# iot-tracker-A.net
KiCad netlist of a schematic drawn in EAGLE
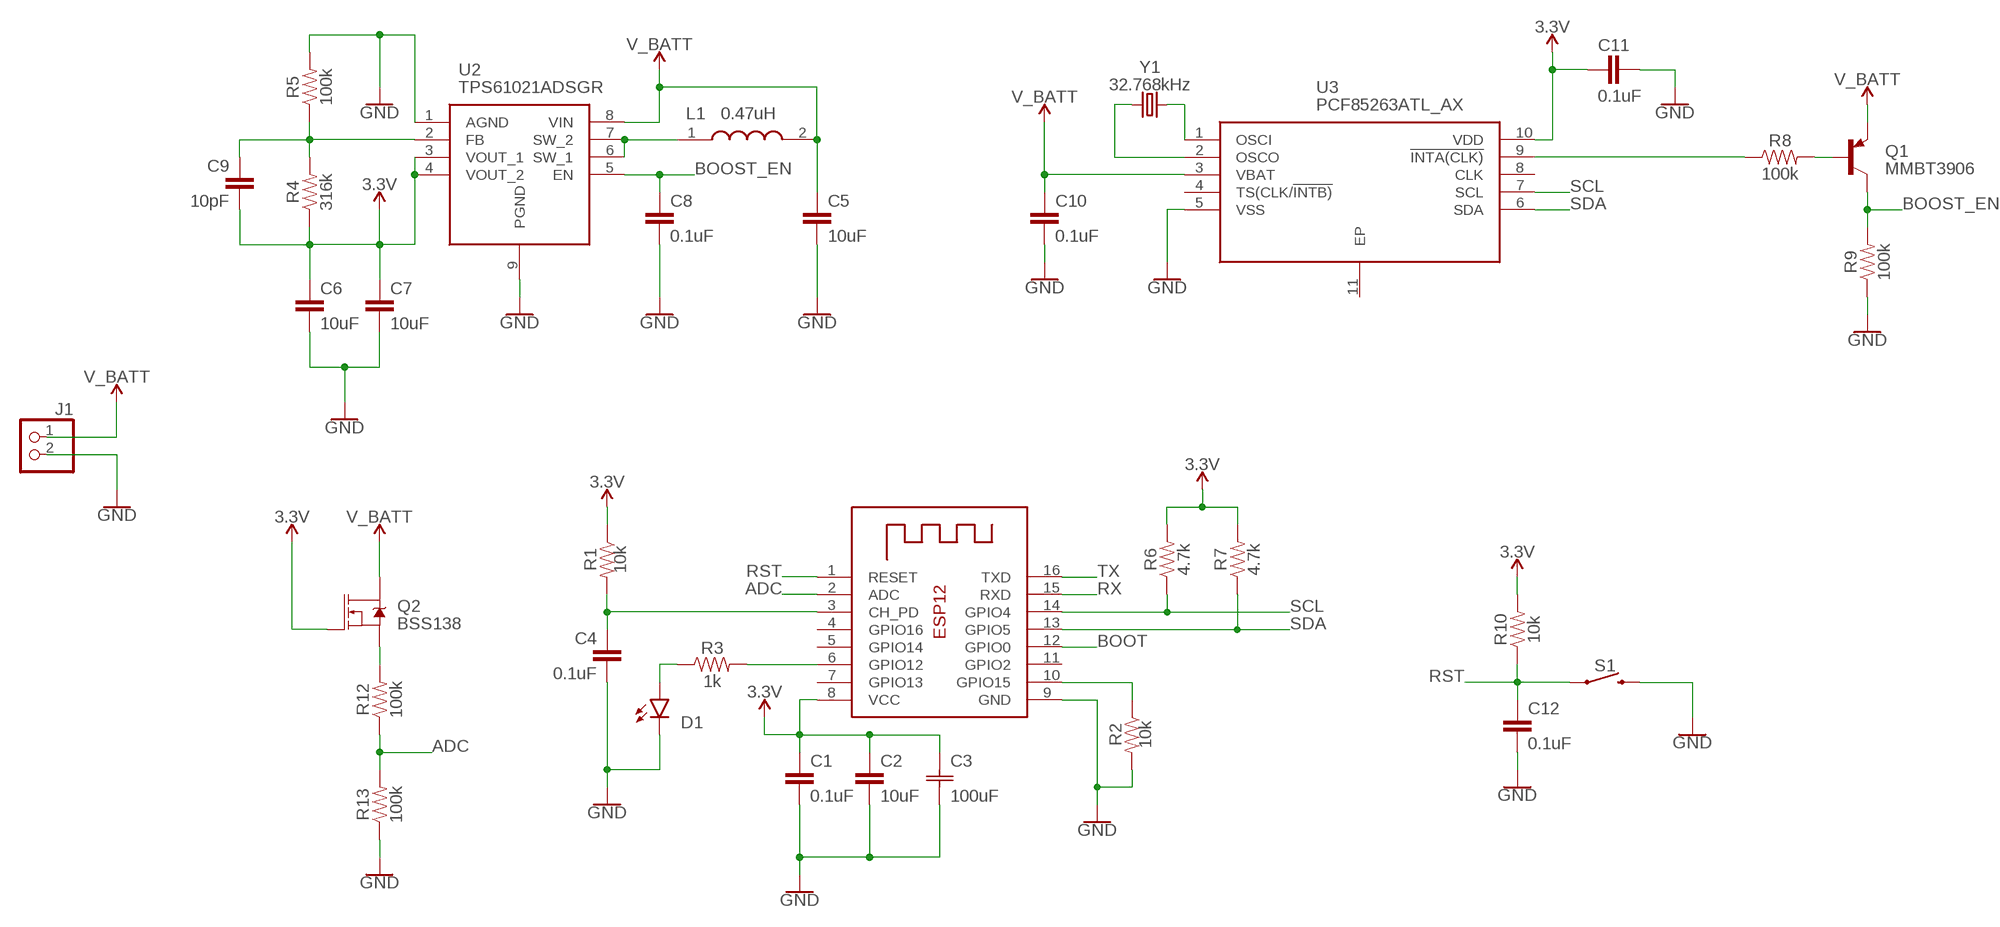
[diagram p0: schematic, sheet 1]

(export (version "E")
  (design (tool "Eeschema 10.0.6"))
  (components
    (comp (ref "C1")
      (value "0.1uF")
      (footprint "eagle-import:0603")
      (libsource (lib "eagle-import") (part "0.1UF-0603-25V-(+80/-20%)"))
    )
    (comp (ref "C2")
      (value "10uF")
      (footprint "eagle-import:0603")
      (libsource (lib "eagle-import") (part "10UF-0603-6.3V-20%"))
    )
    (comp (ref "C3")
      (value "100uF")
      (footprint "eagle-import:F93-C")
      (fields (field (name "MANUFACTURER_PART_NUMBER") "F930J107MBA"))
      (libsource (lib "eagle-import") (part "F930J107MBA"))
    )
    (comp (ref "C4")
      (value "0.1uF")
      (footprint "eagle-import:0603")
      (libsource (lib "eagle-import") (part "0.1UF-0603-25V-(+80/-20%)"))
    )
    (comp (ref "C5")
      (value "10uF")
      (footprint "eagle-import:0603")
      (libsource (lib "eagle-import") (part "10UF-0603-6.3V-20%"))
    )
    (comp (ref "C6")
      (value "10uF")
      (footprint "eagle-import:0603")
      (libsource (lib "eagle-import") (part "10UF-0603-6.3V-20%"))
    )
    (comp (ref "C7")
      (value "10uF")
      (footprint "eagle-import:0603")
      (libsource (lib "eagle-import") (part "10UF-0603-6.3V-20%"))
    )
    (comp (ref "C8")
      (value "0.1uF")
      (footprint "eagle-import:0603")
      (libsource (lib "eagle-import") (part "0.1UF-0603-25V-(+80/-20%)"))
    )
    (comp (ref "C9")
      (value "10pF")
      (footprint "eagle-import:0603")
      (libsource (lib "eagle-import") (part "10PF-0603-50V-5%"))
    )
    (comp (ref "C10")
      (value "0.1uF")
      (footprint "eagle-import:0603")
      (libsource (lib "eagle-import") (part "0.1UF-0603-25V-(+80/-20%)"))
    )
    (comp (ref "C11")
      (value "0.1uF")
      (footprint "eagle-import:0603")
      (libsource (lib "eagle-import") (part "0.1UF-0603-25V-(+80/-20%)"))
    )
    (comp (ref "C12")
      (value "0.1uF")
      (footprint "eagle-import:0603")
      (libsource (lib "eagle-import") (part "0.1UF-0603-25V-(+80/-20%)"))
    )
    (comp (ref "D1")
      (value "LED0603")
      (footprint "eagle-import:LED-0603")
      (libsource (lib "eagle-import") (part "LED0603"))
    )
    (comp (ref "J1")
      (value "PINHD-1X2")
      (footprint "eagle-import:1X02")
      (libsource (lib "eagle-import") (part "PINHD-1X2"))
    )
    (comp (ref "L1")
      (value "0.47uH")
      (footprint "eagle-import:INDC2520X120N")
      (fields
        (field (name "MANUFACTURER_PART_NUMBER") "DFE252012P-R47M=P2")
        (field (name "MOUSER_PART_NUMBER") "81-DFE252012P-R47MP2")
      )
      (libsource (lib "eagle-import") (part "DFE252012P-R47M=P2"))
    )
    (comp (ref "Q1")
      (value "MMBT3906")
      (footprint "eagle-import:SOT23-BEC")
      (libsource (lib "eagle-import") (part "MMBT3906SMDLT1"))
    )
    (comp (ref "Q2")
      (value "BSS138")
      (footprint "eagle-import:SOT23-3")
      (libsource (lib "eagle-import") (part "MOSFET-NCH-BSS138"))
    )
    (comp (ref "R1")
      (value "10k")
      (footprint "eagle-import:0603")
      (libsource (lib "eagle-import") (part "10KOHM-0603-1/10W-1%"))
    )
    (comp (ref "R2")
      (value "10k")
      (footprint "eagle-import:0603")
      (libsource (lib "eagle-import") (part "10KOHM-0603-1/10W-1%"))
    )
    (comp (ref "R3")
      (value "1k")
      (footprint "eagle-import:0603")
      (libsource (lib "eagle-import") (part "1KOHM-0603-1/10W-1%"))
    )
    (comp (ref "R4")
      (value "316k")
      (footprint "eagle-import:0603")
      (libsource (lib "eagle-import") (part "300KOHM-0603-1/10W-1%"))
    )
    (comp (ref "R5")
      (value "100k")
      (footprint "eagle-import:0603")
      (libsource (lib "eagle-import") (part "100KOHM-0603-1/10W-1%"))
    )
    (comp (ref "R6")
      (value "4.7k")
      (footprint "eagle-import:0603")
      (libsource (lib "eagle-import") (part "4.7KOHM-0603-1/10W-1%"))
    )
    (comp (ref "R7")
      (value "4.7k")
      (footprint "eagle-import:0603")
      (libsource (lib "eagle-import") (part "4.7KOHM-0603-1/10W-1%"))
    )
    (comp (ref "R8")
      (value "100k")
      (footprint "eagle-import:0603")
      (libsource (lib "eagle-import") (part "100KOHM-0603-1/10W-1%"))
    )
    (comp (ref "R9")
      (value "100k")
      (footprint "eagle-import:0603")
      (libsource (lib "eagle-import") (part "100KOHM-0603-1/10W-1%"))
    )
    (comp (ref "R10")
      (value "10k")
      (footprint "eagle-import:0603")
      (libsource (lib "eagle-import") (part "10KOHM-0603-1/10W-1%"))
    )
    (comp (ref "R12")
      (value "100k")
      (footprint "eagle-import:0603")
      (libsource (lib "eagle-import") (part "100KOHM-0603-1/10W-1%"))
    )
    (comp (ref "R13")
      (value "100k")
      (footprint "eagle-import:0603")
      (libsource (lib "eagle-import") (part "100KOHM-0603-1/10W-1%"))
    )
    (comp (ref "S1")
      (value "MOMENTARY-SWITCH-SPST-SMD-4.6X2.8MM")
      (footprint "eagle-import:TACTILE_SWITCH_SMD_4.6X2.8MM")
      (libsource (lib "eagle-import") (part "MOMENTARY-SWITCH-SPST-SMD-4.6X2.8MM"))
    )
    (comp (ref "U1")
      (value "ESP-12")
      (footprint "eagle-import:ESP-12")
      (libsource (lib "eagle-import") (part "ESP-12"))
    )
    (comp (ref "U2")
      (value "TPS61021ADSGR")
      (footprint "eagle-import:SON50P200X200X80-9N")
      (fields (field (name "MOUSER_PART_NUMBER") "595-TPS61021ADSGR"))
      (libsource (lib "eagle-import") (part "TPS61021ADSGR"))
    )
    (comp (ref "U3")
      (value "PCF85263ATL_AX")
      (footprint "eagle-import:SON50P260X260X50-11N")
      (fields
        (field (name "MANUFACTURER_PART_NUMBER") "PCF85263ATL/AX")
        (field (name "MOUSER_PART_NUMBER") "771-PCF85263ATL/AX")
      )
      (libsource (lib "eagle-import") (part "PCF85263ATL_AX"))
    )
    (comp (ref "Y1")
      (value "32.768kHz")
      (footprint "eagle-import:CRYSTAL-SMD-3.2X1.5MM")
      (libsource (lib "eagle-import") (part "CRYSTAL-32.768KHZSMD-3.2X1.5"))
    )
  )
  (nets
    (net (code "1") (name "/ADC") (class "Default")
      (node (ref "R12") (pin "1") (pinfunction "1_1") (pintype "passive"))
      (node (ref "R13") (pin "2") (pinfunction "2_2") (pintype "passive"))
      (node (ref "U1") (pin "2") (pinfunction "ADC_2") (pintype "passive"))
    )
    (net (code "2") (name "/BOOST_EN") (class "Default")
      (node (ref "C8") (pin "1") (pinfunction "1_1") (pintype "passive"))
      (node (ref "Q1") (pin "C") (pinfunction "C_C") (pintype "passive"))
      (node (ref "R9") (pin "2") (pinfunction "2_2") (pintype "passive"))
      (node (ref "U2") (pin "5") (pinfunction "EN_5") (pintype "input"))
    )
    (net (code "3") (name "/BOOT") (class "Default")
      (node (ref "U1") (pin "12") (pinfunction "GPIO0_12") (pintype "bidirectional"))
    )
    (net (code "4") (name "/RST") (class "Default")
      (node (ref "C12") (pin "1") (pinfunction "1_1") (pintype "passive"))
      (node (ref "R10") (pin "1") (pinfunction "1_1") (pintype "passive"))
      (node (ref "S1") (pin "1") (pinfunction "1_1") (pintype "passive"))
      (node (ref "S1") (pin "2") (pinfunction "1_2") (pintype "passive"))
      (node (ref "U1") (pin "1") (pinfunction "RESET_1") (pintype "input"))
    )
    (net (code "5") (name "/RX") (class "Default")
      (node (ref "U1") (pin "15") (pinfunction "RXD_15") (pintype "input"))
    )
    (net (code "6") (name "/SCL") (class "Default")
      (node (ref "R6") (pin "1") (pinfunction "1_1") (pintype "passive"))
      (node (ref "U1") (pin "14") (pinfunction "GPIO4_14") (pintype "bidirectional"))
      (node (ref "U3") (pin "7") (pinfunction "SCL_7") (pintype "bidirectional"))
    )
    (net (code "7") (name "/SDA") (class "Default")
      (node (ref "R7") (pin "1") (pinfunction "1_1") (pintype "passive"))
      (node (ref "U1") (pin "13") (pinfunction "GPIO5_13") (pintype "bidirectional"))
      (node (ref "U3") (pin "6") (pinfunction "SDA_6") (pintype "bidirectional"))
    )
    (net (code "8") (name "/TX") (class "Default")
      (node (ref "U1") (pin "16") (pinfunction "TXD_16") (pintype "output"))
    )
    (net (code "9") (name "3.3V") (class "Default")
      (node (ref "C1") (pin "1") (pinfunction "1_1") (pintype "passive"))
      (node (ref "C11") (pin "2") (pinfunction "2_2") (pintype "passive"))
      (node (ref "C2") (pin "1") (pinfunction "1_1") (pintype "passive"))
      (node (ref "C3") (pin "1") (pinfunction "1_1") (pintype "passive"))
      (node (ref "C6") (pin "1") (pinfunction "1_1") (pintype "passive"))
      (node (ref "C7") (pin "1") (pinfunction "1_1") (pintype "passive"))
      (node (ref "C9") (pin "2") (pinfunction "2_2") (pintype "passive"))
      (node (ref "Q2") (pin "1") (pinfunction "G_1") (pintype "bidirectional"))
      (node (ref "R1") (pin "1") (pinfunction "1_1") (pintype "passive"))
      (node (ref "R10") (pin "2") (pinfunction "2_2") (pintype "passive"))
      (node (ref "R4") (pin "1") (pinfunction "1_1") (pintype "passive"))
      (node (ref "R6") (pin "2") (pinfunction "2_2") (pintype "passive"))
      (node (ref "R7") (pin "2") (pinfunction "2_2") (pintype "passive"))
      (node (ref "U1") (pin "8") (pinfunction "VCC_8") (pintype "power_in"))
      (node (ref "U2") (pin "3") (pinfunction "VOUT_1_3") (pintype "power_in"))
      (node (ref "U2") (pin "4") (pinfunction "VOUT_2_4") (pintype "power_in"))
      (node (ref "U3") (pin "10") (pinfunction "VDD_10") (pintype "power_in"))
    )
    (net (code "10") (name "GND") (class "Default")
      (node (ref "C1") (pin "2") (pinfunction "2_2") (pintype "passive"))
      (node (ref "C10") (pin "2") (pinfunction "2_2") (pintype "passive"))
      (node (ref "C11") (pin "1") (pinfunction "1_1") (pintype "passive"))
      (node (ref "C12") (pin "2") (pinfunction "2_2") (pintype "passive"))
      (node (ref "C2") (pin "2") (pinfunction "2_2") (pintype "passive"))
      (node (ref "C3") (pin "2") (pinfunction "2_2") (pintype "passive"))
      (node (ref "C4") (pin "2") (pinfunction "2_2") (pintype "passive"))
      (node (ref "C5") (pin "2") (pinfunction "2_2") (pintype "passive"))
      (node (ref "C6") (pin "2") (pinfunction "2_2") (pintype "passive"))
      (node (ref "C7") (pin "2") (pinfunction "2_2") (pintype "passive"))
      (node (ref "C8") (pin "2") (pinfunction "2_2") (pintype "passive"))
      (node (ref "D1") (pin "C") (pinfunction "C_C") (pintype "passive"))
      (node (ref "J1") (pin "2") (pinfunction "2_2") (pintype "passive"))
      (node (ref "R13") (pin "1") (pinfunction "1_1") (pintype "passive"))
      (node (ref "R2") (pin "2") (pinfunction "2_2") (pintype "passive"))
      (node (ref "R5") (pin "2") (pinfunction "2_2") (pintype "passive"))
      (node (ref "R9") (pin "1") (pinfunction "1_1") (pintype "passive"))
      (node (ref "S1") (pin "3") (pinfunction "2_3") (pintype "passive"))
      (node (ref "S1") (pin "4") (pinfunction "2_4") (pintype "passive"))
      (node (ref "U1") (pin "9") (pinfunction "GND_9") (pintype "power_in"))
      (node (ref "U2") (pin "1") (pinfunction "AGND_1") (pintype "power_in"))
      (node (ref "U2") (pin "9") (pinfunction "PGND_9") (pintype "power_in"))
      (node (ref "U3") (pin "5") (pinfunction "VSS_5") (pintype "power_in"))
    )
    (net (code "11") (name "Net-(D1-PadA)") (class "Default")
      (node (ref "D1") (pin "A") (pinfunction "A_A") (pintype "passive"))
      (node (ref "R3") (pin "1") (pinfunction "1_1") (pintype "passive"))
    )
    (net (code "12") (name "Net-(Q1-PadB)") (class "Default")
      (node (ref "Q1") (pin "B") (pinfunction "B_B") (pintype "passive"))
      (node (ref "R8") (pin "2") (pinfunction "2_2") (pintype "passive"))
    )
    (net (code "13") (name "Net-(Q2-S)") (class "Default")
      (node (ref "Q2") (pin "2") (pinfunction "S_2") (pintype "bidirectional"))
      (node (ref "R12") (pin "2") (pinfunction "2_2") (pintype "passive"))
    )
    (net (code "14") (name "Net-(U1-CH_PD)") (class "Default")
      (node (ref "C4") (pin "1") (pinfunction "1_1") (pintype "passive"))
      (node (ref "R1") (pin "2") (pinfunction "2_2") (pintype "passive"))
      (node (ref "U1") (pin "3") (pinfunction "CH_PD_3") (pintype "input"))
    )
    (net (code "15") (name "Net-(U1-GPIO12)") (class "Default")
      (node (ref "R3") (pin "2") (pinfunction "2_2") (pintype "passive"))
      (node (ref "U1") (pin "6") (pinfunction "GPIO12_6") (pintype "bidirectional"))
    )
    (net (code "16") (name "Net-(U1-GPIO15)") (class "Default")
      (node (ref "R2") (pin "1") (pinfunction "1_1") (pintype "passive"))
      (node (ref "U1") (pin "10") (pinfunction "GPIO15_10") (pintype "bidirectional"))
    )
    (net (code "17") (name "Net-(U2-FB)") (class "Default")
      (node (ref "C9") (pin "1") (pinfunction "1_1") (pintype "passive"))
      (node (ref "R4") (pin "2") (pinfunction "2_2") (pintype "passive"))
      (node (ref "R5") (pin "1") (pinfunction "1_1") (pintype "passive"))
      (node (ref "U2") (pin "2") (pinfunction "FB_2") (pintype "input"))
    )
    (net (code "18") (name "Net-(U2-SW_1)") (class "Default")
      (node (ref "L1") (pin "1") (pinfunction "1_1") (pintype "bidirectional"))
      (node (ref "U2") (pin "6") (pinfunction "SW_1_6") (pintype "power_in"))
      (node (ref "U2") (pin "7") (pinfunction "SW_2_7") (pintype "power_in"))
    )
    (net (code "19") (name "Net-(U3-OSCI)") (class "Default")
      (node (ref "U3") (pin "1") (pinfunction "OSCI_1") (pintype "bidirectional"))
      (node (ref "Y1") (pin "P$2") (pinfunction "2_P$2") (pintype "passive"))
    )
    (net (code "20") (name "Net-(U3-OSCO)") (class "Default")
      (node (ref "U3") (pin "2") (pinfunction "OSCO_2") (pintype "bidirectional"))
      (node (ref "Y1") (pin "P$1") (pinfunction "1_P$1") (pintype "passive"))
    )
    (net (code "21") (name "Net-(U3-~{INTA(CLK}))") (class "Default")
      (node (ref "R8") (pin "1") (pinfunction "1_1") (pintype "passive"))
      (node (ref "U3") (pin "9") (pinfunction "~{INTA(CLK})_9") (pintype "input"))
    )
    (net (code "22") (name "V_BATT") (class "Default")
      (node (ref "C10") (pin "1") (pinfunction "1_1") (pintype "passive"))
      (node (ref "C5") (pin "1") (pinfunction "1_1") (pintype "passive"))
      (node (ref "J1") (pin "1") (pinfunction "1_1") (pintype "passive"))
      (node (ref "L1") (pin "2") (pinfunction "2_2") (pintype "bidirectional"))
      (node (ref "Q1") (pin "E") (pinfunction "E_E") (pintype "passive"))
      (node (ref "Q2") (pin "3") (pinfunction "D_3") (pintype "bidirectional"))
      (node (ref "U2") (pin "8") (pinfunction "VIN_8") (pintype "input"))
      (node (ref "U3") (pin "3") (pinfunction "VBAT_3") (pintype "bidirectional"))
    )
    (net (code "23") (name "unconnected-(U1-GPIO2-Pad11)") (class "Default")
      (node (ref "U1") (pin "11") (pinfunction "GPIO2_11") (pintype "bidirectional"))
    )
    (net (code "24") (name "unconnected-(U1-GPIO13-Pad7)") (class "Default")
      (node (ref "U1") (pin "7") (pinfunction "GPIO13_7") (pintype "bidirectional"))
    )
    (net (code "25") (name "unconnected-(U1-GPIO14-Pad5)") (class "Default")
      (node (ref "U1") (pin "5") (pinfunction "GPIO14_5") (pintype "bidirectional"))
    )
    (net (code "26") (name "unconnected-(U1-GPIO16-Pad4)") (class "Default")
      (node (ref "U1") (pin "4") (pinfunction "GPIO16_4") (pintype "bidirectional"))
    )
    (net (code "27") (name "unconnected-(U3-CLK-Pad8)") (class "Default")
      (node (ref "U3") (pin "8") (pinfunction "CLK_8") (pintype "input"))
    )
    (net (code "28") (name "unconnected-(U3-EP-Pad11)") (class "Default")
      (node (ref "U3") (pin "11") (pinfunction "EP_11") (pintype "bidirectional"))
    )
    (net (code "29") (name "unconnected-(U3-TS(CLK{slash}~{INTB})-Pad4)") (class "Default")
      (node (ref "U3") (pin "4") (pinfunction "TS(CLK/~{INTB})_4") (pintype "input"))
    )
  )
)
